# main_module.net
KiCad netlist of a schematic drawn in EAGLE
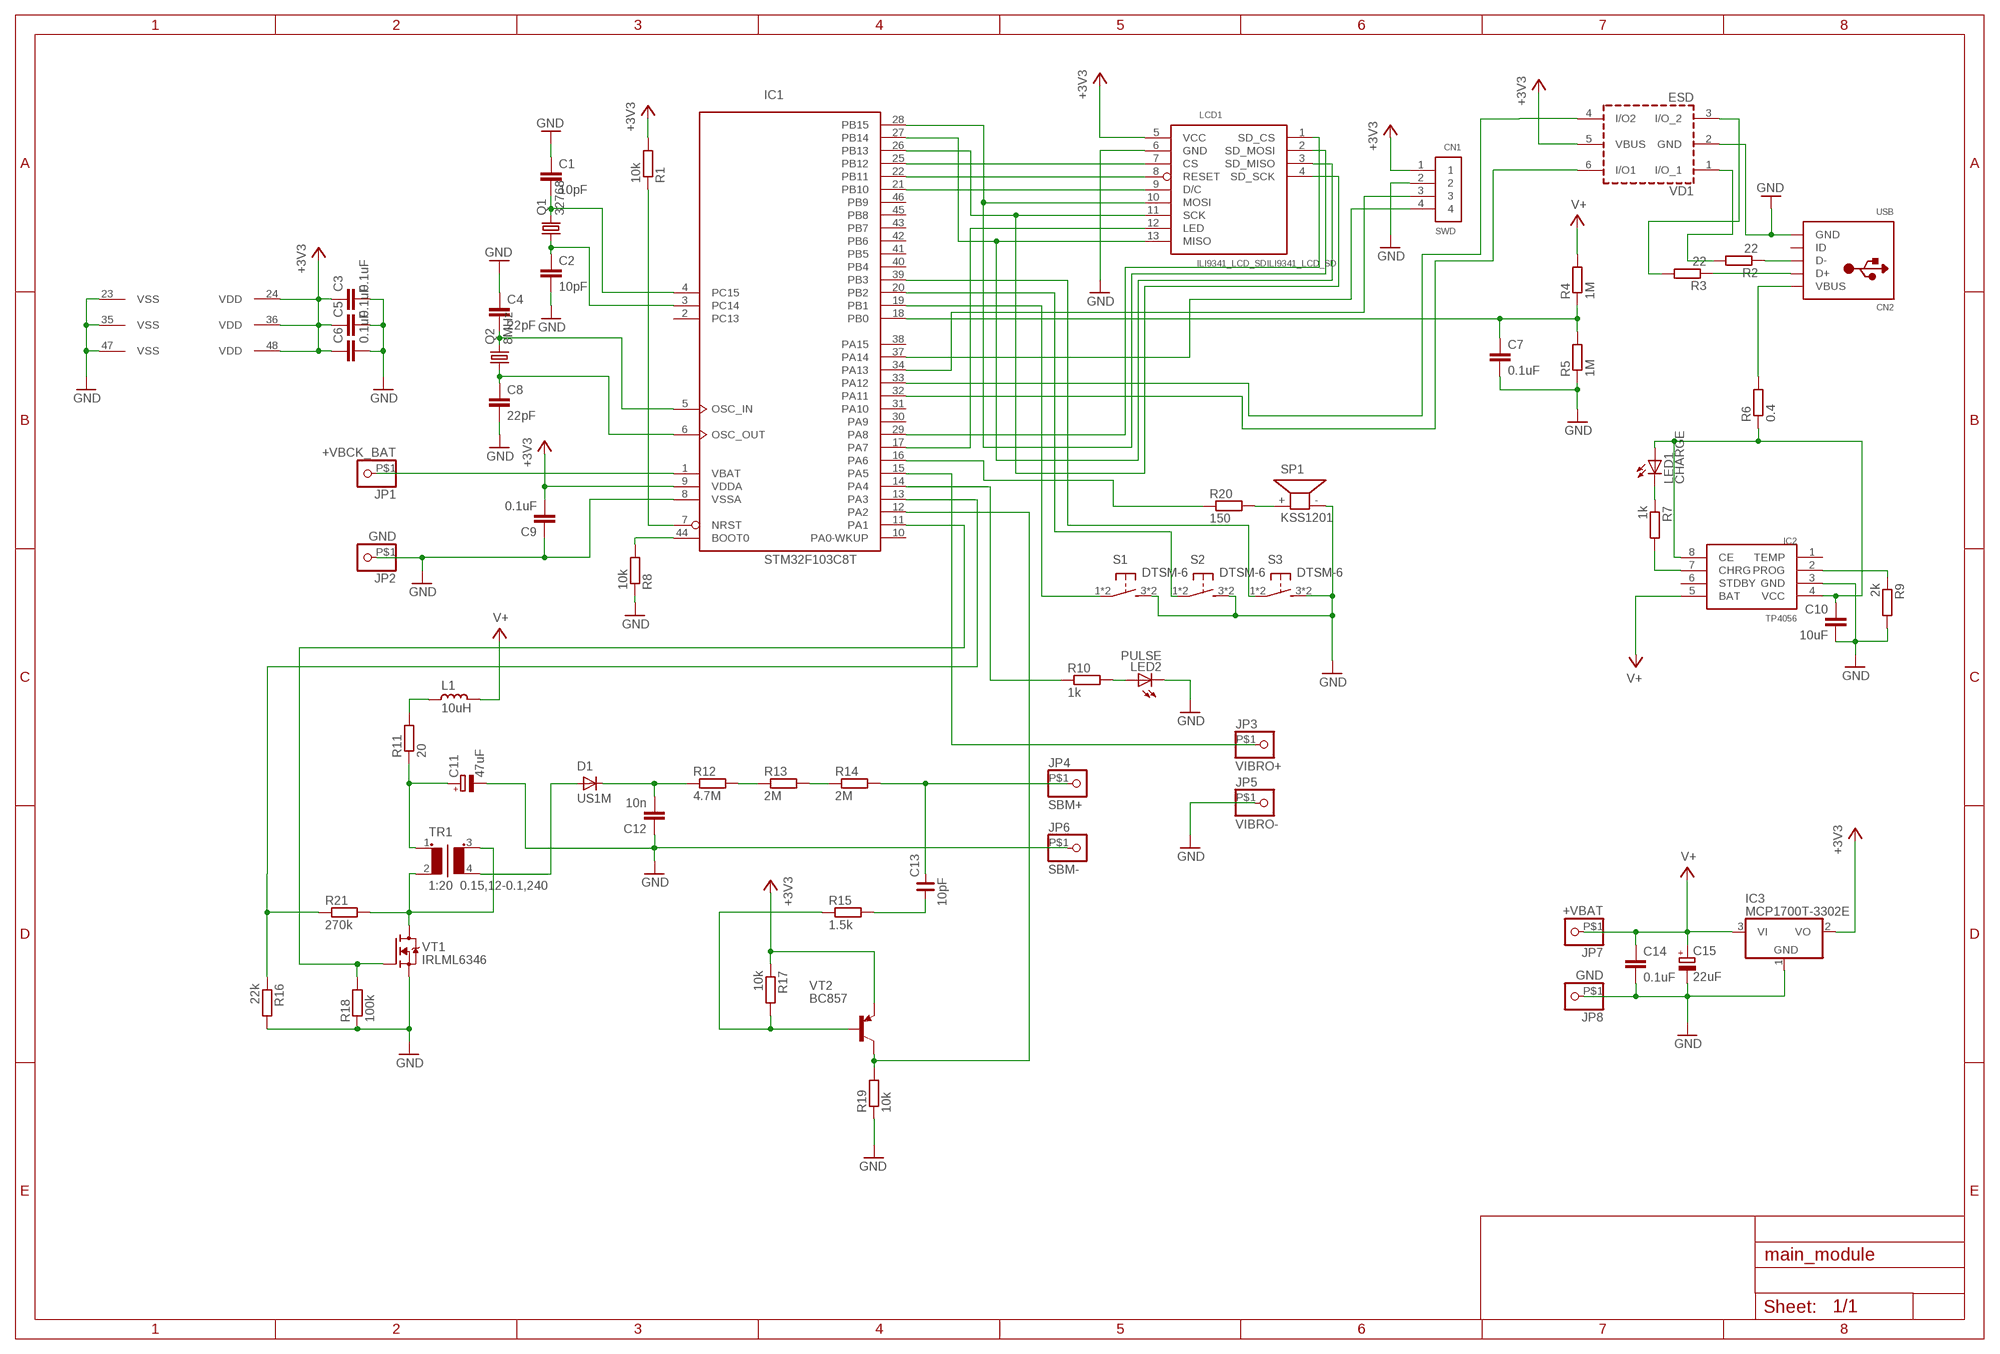
[diagram p0: schematic, sheet 1]

(export (version "E")
  (design (tool "Eeschema 10.0.6"))
  (components
    (comp (ref "C1")
      (value "10pF")
      (footprint "eagle-import:C0805")
      (libsource (lib "eagle-import") (part "C-EUC0805"))
    )
    (comp (ref "C2")
      (value "10pF")
      (footprint "eagle-import:C0805")
      (libsource (lib "eagle-import") (part "C-EUC0805"))
    )
    (comp (ref "C3")
      (value "0.1uF")
      (footprint "eagle-import:C0805")
      (libsource (lib "eagle-import") (part "C-EUC0805"))
    )
    (comp (ref "C4")
      (value "22pF")
      (footprint "eagle-import:C0805")
      (libsource (lib "eagle-import") (part "C-EUC0805"))
    )
    (comp (ref "C5")
      (value "0.1uF")
      (footprint "eagle-import:C0805")
      (libsource (lib "eagle-import") (part "C-EUC0805"))
    )
    (comp (ref "C6")
      (value "0.1uF")
      (footprint "eagle-import:C0805")
      (libsource (lib "eagle-import") (part "C-EUC0805"))
    )
    (comp (ref "C7")
      (value "0.1uF")
      (footprint "eagle-import:C0805")
      (libsource (lib "eagle-import") (part "C-EUC0805"))
    )
    (comp (ref "C8")
      (value "22pF")
      (footprint "eagle-import:C0805")
      (libsource (lib "eagle-import") (part "C-EUC0805"))
    )
    (comp (ref "C9")
      (value "0.1uF")
      (footprint "eagle-import:C0805")
      (libsource (lib "eagle-import") (part "C-EUC0805"))
    )
    (comp (ref "C10")
      (value "10uF")
      (footprint "eagle-import:C0805")
      (libsource (lib "eagle-import") (part "C-EUC0805"))
    )
    (comp (ref "C11")
      (value "47uF")
      (footprint "eagle-import:C_6032-28R")
      (libsource (lib "eagle-import") (part "CPOL-EUC/6032-28R"))
    )
    (comp (ref "C12")
      (value "10n")
      (footprint "eagle-import:C1206")
      (libsource (lib "eagle-import") (part "C-EUC1206"))
    )
    (comp (ref "C13")
      (value "10pF")
      (footprint "eagle-import:C1206")
      (libsource (lib "eagle-import") (part "C_1206"))
    )
    (comp (ref "C14")
      (value "0.1uF")
      (footprint "eagle-import:C0805")
      (libsource (lib "eagle-import") (part "C-EUC0805"))
    )
    (comp (ref "C15")
      (value "22uF")
      (footprint "eagle-import:C_6032-28R")
      (libsource (lib "eagle-import") (part "CPOL-EUC/6032-28R"))
    )
    (comp (ref "CN1")
      (value "SWD")
      (footprint "eagle-import:1X04-BIG")
      (libsource (lib "eagle-import") (part "1X4-BIG"))
    )
    (comp (ref "CN2")
      (value "USB")
      (footprint "eagle-import:USB-MINIB")
      (libsource (lib "eagle-import") (part "USBMINIB"))
    )
    (comp (ref "D1")
      (value "US1M")
      (footprint "eagle-import:SMA-DO214AC")
      (libsource (lib "eagle-import") (part "GF1"))
    )
    (comp (ref "IC1")
      (value "STM32F103C8T")
      (footprint "eagle-import:LQFP48")
      (libsource (lib "eagle-import") (part "STM32F103CT8"))
    )
    (comp (ref "IC2")
      (value "TP4056")
      (footprint "eagle-import:SOP-8")
      (libsource (lib "eagle-import") (part "TP4056"))
    )
    (comp (ref "IC3")
      (value "MCP1700T-3302E")
      (footprint "eagle-import:SOT23")
      (libsource (lib "eagle-import") (part "MCP1703CB"))
    )
    (comp (ref "JP1")
      (value "+VBCK_BAT")
      (footprint "eagle-import:1X1-BIGPOGO")
      (libsource (lib "eagle-import") (part "PINHD-1X1-BIGPOGO"))
    )
    (comp (ref "JP2")
      (value "GND")
      (footprint "eagle-import:1X1-BIGPOGO")
      (libsource (lib "eagle-import") (part "PINHD-1X1-BIGPOGO"))
    )
    (comp (ref "JP3")
      (value "VIBRO+")
      (footprint "eagle-import:1X1-BIGPOGO")
      (libsource (lib "eagle-import") (part "PINHD-1X1-BIGPOGO"))
    )
    (comp (ref "JP4")
      (value "SBM+")
      (footprint "eagle-import:1X1-BIGPOGO")
      (libsource (lib "eagle-import") (part "PINHD-1X1-BIGPOGO"))
    )
    (comp (ref "JP5")
      (value "VIBRO-")
      (footprint "eagle-import:1X1-BIGPOGO")
      (libsource (lib "eagle-import") (part "PINHD-1X1-BIGPOGO"))
    )
    (comp (ref "JP6")
      (value "SBM-")
      (footprint "eagle-import:1X1-BIGPOGO")
      (libsource (lib "eagle-import") (part "PINHD-1X1-BIGPOGO"))
    )
    (comp (ref "JP7")
      (value "+VBAT")
      (footprint "eagle-import:1X1-BIGPOGO")
      (libsource (lib "eagle-import") (part "PINHD-1X1-BIGPOGO"))
    )
    (comp (ref "JP8")
      (value "GND")
      (footprint "eagle-import:1X1-BIGPOGO")
      (libsource (lib "eagle-import") (part "PINHD-1X1-BIGPOGO"))
    )
    (comp (ref "L1")
      (value "10uH")
      (footprint "eagle-import:L0805")
      (libsource (lib "eagle-import") (part "L_0805"))
    )
    (comp (ref "LCD1")
      (value "ILI9341_LCD_SDILI9341_LCD_SD")
      (footprint "eagle-import:ILI9341_LCD_SD")
      (libsource (lib "eagle-import") (part "ILI9341_LCD_SDILI9341_LCD_SD"))
    )
    (comp (ref "LED1")
      (value "CHARGE")
      (footprint "eagle-import:CHIP-LED0805")
      (libsource (lib "eagle-import") (part "led_LEDCHIP-LED0805"))
    )
    (comp (ref "LED2")
      (value "PULSE")
      (footprint "eagle-import:LED3MM")
      (libsource (lib "eagle-import") (part "LED3MM"))
    )
    (comp (ref "Q1")
      (value "32768")
      (footprint "eagle-import:HC49_S")
      (libsource (lib "eagle-import") (part "CRYSTALHC49S"))
    )
    (comp (ref "Q2")
      (value "8MHz")
      (footprint "eagle-import:HC49_S")
      (libsource (lib "eagle-import") (part "CRYSTALHC49S"))
    )
    (comp (ref "R1")
      (value "10k")
      (footprint "eagle-import:M0805")
      (libsource (lib "eagle-import") (part "R-EU_M0805"))
    )
    (comp (ref "R2")
      (value "22")
      (footprint "eagle-import:M0805")
      (libsource (lib "eagle-import") (part "R-EU_M0805"))
    )
    (comp (ref "R3")
      (value "22")
      (footprint "eagle-import:M0805")
      (libsource (lib "eagle-import") (part "R-EU_M0805"))
    )
    (comp (ref "R4")
      (value "1M")
      (footprint "eagle-import:M0805")
      (libsource (lib "eagle-import") (part "R-EU_M0805"))
    )
    (comp (ref "R5")
      (value "1M")
      (footprint "eagle-import:M0805")
      (libsource (lib "eagle-import") (part "R-EU_M0805"))
    )
    (comp (ref "R6")
      (value "0.4")
      (footprint "eagle-import:M1206")
      (libsource (lib "eagle-import") (part "R-EU_M1206"))
    )
    (comp (ref "R7")
      (value "1k")
      (footprint "eagle-import:M0805")
      (libsource (lib "eagle-import") (part "R-EU_M0805"))
    )
    (comp (ref "R8")
      (value "10k")
      (footprint "eagle-import:M0805")
      (libsource (lib "eagle-import") (part "R-EU_M0805"))
    )
    (comp (ref "R9")
      (value "2k")
      (footprint "eagle-import:M0805")
      (libsource (lib "eagle-import") (part "R-EU_M0805"))
    )
    (comp (ref "R10")
      (value "1k")
      (footprint "eagle-import:M0805")
      (libsource (lib "eagle-import") (part "R-EU_M0805"))
    )
    (comp (ref "R11")
      (value "20")
      (footprint "eagle-import:M0805")
      (libsource (lib "eagle-import") (part "R-EU_M0805"))
    )
    (comp (ref "R12")
      (value "4.7M")
      (footprint "eagle-import:M0805")
      (libsource (lib "eagle-import") (part "R-EU_M0805"))
    )
    (comp (ref "R13")
      (value "2M")
      (footprint "eagle-import:M0805")
      (libsource (lib "eagle-import") (part "R-EU_M0805"))
    )
    (comp (ref "R14")
      (value "2M")
      (footprint "eagle-import:M0805")
      (libsource (lib "eagle-import") (part "R-EU_M0805"))
    )
    (comp (ref "R15")
      (value "1.5k")
      (footprint "eagle-import:M0805")
      (libsource (lib "eagle-import") (part "R-EU_M0805"))
    )
    (comp (ref "R16")
      (value "22k")
      (footprint "eagle-import:M0805")
      (libsource (lib "eagle-import") (part "R-EU_M0805"))
    )
    (comp (ref "R17")
      (value "10k")
      (footprint "eagle-import:M0805")
      (libsource (lib "eagle-import") (part "R-EU_M0805"))
    )
    (comp (ref "R18")
      (value "100k")
      (footprint "eagle-import:M0805")
      (libsource (lib "eagle-import") (part "R-EU_M0805"))
    )
    (comp (ref "R19")
      (value "10k")
      (footprint "eagle-import:M0805")
      (libsource (lib "eagle-import") (part "R-EU_M0805"))
    )
    (comp (ref "R20")
      (value "150")
      (footprint "eagle-import:M0805")
      (libsource (lib "eagle-import") (part "R-EU_M0805"))
    )
    (comp (ref "R21")
      (value "270k")
      (footprint "eagle-import:M0805")
      (libsource (lib "eagle-import") (part "R-EU_M0805"))
    )
    (comp (ref "S1")
      (value "DTSM-6")
      (footprint "eagle-import:DTSM-6")
      (libsource (lib "eagle-import") (part "DTSM-6"))
    )
    (comp (ref "S2")
      (value "DTSM-6")
      (footprint "eagle-import:DTSM-6")
      (libsource (lib "eagle-import") (part "DTSM-6"))
    )
    (comp (ref "S3")
      (value "DTSM-6")
      (footprint "eagle-import:DTSM-6")
      (libsource (lib "eagle-import") (part "DTSM-6"))
    )
    (comp (ref "SP1")
      (value "KSS1201")
      (footprint "eagle-import:KSS1201")
      (libsource (lib "eagle-import") (part "KSS1201"))
    )
    (comp (ref "TR1")
      (value "1:20 0.15,12-0.1,240")
      (footprint "eagle-import:RING-TRANS")
      (libsource (lib "eagle-import") (part "RING-TRANS"))
    )
    (comp (ref "VD1")
      (value "ESD")
      (footprint "eagle-import:SOT-23-6L")
      (libsource (lib "eagle-import") (part "USBLC6-2SC6"))
    )
    (comp (ref "VT1")
      (value "IRLML6346")
      (footprint "eagle-import:SOT23")
      (libsource (lib "eagle-import") (part "MOSFET-N-SOT23"))
    )
    (comp (ref "VT2")
      (value "BC857")
      (footprint "eagle-import:SOT23-BCE")
      (libsource (lib "eagle-import") (part "-PNP-SOT23-BCE"))
    )
  )
  (nets
    (net (code "1") (name "+3V3") (class "Default")
      (node (ref "C3") (pin "1") (pinfunction "1_1") (pintype "passive"))
      (node (ref "C5") (pin "1") (pinfunction "1_1") (pintype "passive"))
      (node (ref "C6") (pin "1") (pinfunction "1_1") (pintype "passive"))
      (node (ref "C9") (pin "2") (pinfunction "2_2") (pintype "passive"))
      (node (ref "CN1") (pin "1") (pinfunction "1_1") (pintype "bidirectional"))
      (node (ref "IC1") (pin "24") (pinfunction "VDD_24") (pintype "power_in"))
      (node (ref "IC1") (pin "36") (pinfunction "VDD_36") (pintype "power_in"))
      (node (ref "IC1") (pin "48") (pinfunction "VDD_48") (pintype "power_in"))
      (node (ref "IC1") (pin "9") (pinfunction "VDDA_9") (pintype "power_in"))
      (node (ref "IC3") (pin "2") (pinfunction "VO_2") (pintype "passive"))
      (node (ref "LCD1") (pin "5") (pinfunction "VCC_5") (pintype "power_in"))
      (node (ref "R1") (pin "2") (pinfunction "2_2") (pintype "passive"))
      (node (ref "R17") (pin "1") (pinfunction "1_1") (pintype "passive"))
      (node (ref "VD1") (pin "5") (pinfunction "VBUS_5") (pintype "bidirectional"))
      (node (ref "VT2") (pin "E") (pinfunction "E_E") (pintype "passive"))
    )
    (net (code "2") (name "GND") (class "Default")
      (node (ref "C1") (pin "1") (pinfunction "1_1") (pintype "passive"))
      (node (ref "C10") (pin "2") (pinfunction "2_2") (pintype "passive"))
      (node (ref "C11") (pin "-") (pinfunction "-_-") (pintype "passive"))
      (node (ref "C12") (pin "1") (pinfunction "1_1") (pintype "passive"))
      (node (ref "C14") (pin "2") (pinfunction "2_2") (pintype "passive"))
      (node (ref "C15") (pin "-") (pinfunction "-_-") (pintype "passive"))
      (node (ref "C2") (pin "2") (pinfunction "2_2") (pintype "passive"))
      (node (ref "C3") (pin "2") (pinfunction "2_2") (pintype "passive"))
      (node (ref "C4") (pin "1") (pinfunction "1_1") (pintype "passive"))
      (node (ref "C5") (pin "2") (pinfunction "2_2") (pintype "passive"))
      (node (ref "C6") (pin "2") (pinfunction "2_2") (pintype "passive"))
      (node (ref "C7") (pin "2") (pinfunction "2_2") (pintype "passive"))
      (node (ref "C8") (pin "2") (pinfunction "2_2") (pintype "passive"))
      (node (ref "C9") (pin "1") (pinfunction "1_1") (pintype "passive"))
      (node (ref "CN1") (pin "2") (pinfunction "2_2") (pintype "bidirectional"))
      (node (ref "CN2") (pin "GND") (pinfunction "GND_GND") (pintype "power_in"))
      (node (ref "IC1") (pin "23") (pinfunction "VSS_23") (pintype "power_in"))
      (node (ref "IC1") (pin "35") (pinfunction "VSS_35") (pintype "power_in"))
      (node (ref "IC1") (pin "47") (pinfunction "VSS_47") (pintype "power_in"))
      (node (ref "IC1") (pin "8") (pinfunction "VSSA_8") (pintype "power_in"))
      (node (ref "IC2") (pin "3") (pinfunction "GND_3") (pintype "bidirectional"))
      (node (ref "IC3") (pin "1") (pinfunction "GND_1") (pintype "passive"))
      (node (ref "JP2") (pin "P$1") (pinfunction "1_P$1") (pintype "passive"))
      (node (ref "JP5") (pin "P$1") (pinfunction "1_P$1") (pintype "passive"))
      (node (ref "JP6") (pin "P$1") (pinfunction "1_P$1") (pintype "passive"))
      (node (ref "JP8") (pin "P$1") (pinfunction "1_P$1") (pintype "passive"))
      (node (ref "LCD1") (pin "6") (pinfunction "GND_6") (pintype "power_in"))
      (node (ref "LED2") (pin "K") (pinfunction "C_K") (pintype "passive"))
      (node (ref "R16") (pin "2") (pinfunction "2_2") (pintype "passive"))
      (node (ref "R18") (pin "1") (pinfunction "1_1") (pintype "passive"))
      (node (ref "R19") (pin "1") (pinfunction "1_1") (pintype "passive"))
      (node (ref "R5") (pin "1") (pinfunction "1_1") (pintype "passive"))
      (node (ref "R8") (pin "1") (pinfunction "1_1") (pintype "passive"))
      (node (ref "R9") (pin "2") (pinfunction "2_2") (pintype "passive"))
      (node (ref "S1") (pin "3") (pinfunction "3_3") (pintype "passive"))
      (node (ref "S1") (pin "4") (pinfunction "3_4") (pintype "passive"))
      (node (ref "S2") (pin "3") (pinfunction "3_3") (pintype "passive"))
      (node (ref "S2") (pin "4") (pinfunction "3_4") (pintype "passive"))
      (node (ref "S3") (pin "3") (pinfunction "3_3") (pintype "passive"))
      (node (ref "S3") (pin "4") (pinfunction "3_4") (pintype "passive"))
      (node (ref "SP1") (pin "-") (pinfunction "2_-") (pintype "passive"))
      (node (ref "VD1") (pin "2") (pinfunction "GND_2") (pintype "bidirectional"))
      (node (ref "VT1") (pin "2") (pinfunction "S_2") (pintype "passive"))
    )
    (net (code "3") (name "Net-(C13-Pad1)") (class "Default")
      (node (ref "C13") (pin "1") (pinfunction "1_1") (pintype "passive"))
      (node (ref "R15") (pin "2") (pinfunction "2_2") (pintype "passive"))
    )
    (net (code "4") (name "Net-(CN2-PadD+)") (class "Default")
      (node (ref "CN2") (pin "D+") (pinfunction "D+_D+") (pintype "bidirectional"))
      (node (ref "R3") (pin "1") (pinfunction "1_1") (pintype "passive"))
    )
    (net (code "5") (name "Net-(CN2-PadD-)") (class "Default")
      (node (ref "CN2") (pin "D-") (pinfunction "D-_D-") (pintype "bidirectional"))
      (node (ref "R2") (pin "1") (pinfunction "1_1") (pintype "passive"))
    )
    (net (code "6") (name "Net-(CN2-PadVBUS)") (class "Default")
      (node (ref "CN2") (pin "VBUS") (pinfunction "VBUS_VBUS") (pintype "power_in"))
      (node (ref "R6") (pin "2") (pinfunction "2_2") (pintype "passive"))
    )
    (net (code "7") (name "Net-(D1-C)") (class "Default")
      (node (ref "C12") (pin "2") (pinfunction "2_2") (pintype "passive"))
      (node (ref "D1") (pin "K") (pinfunction "C_K") (pintype "passive"))
      (node (ref "R12") (pin "1") (pinfunction "1_1") (pintype "passive"))
    )
    (net (code "8") (name "Net-(IC1A-BOOT0)") (class "Default")
      (node (ref "IC1") (pin "44") (pinfunction "BOOT0_44") (pintype "input"))
      (node (ref "R8") (pin "2") (pinfunction "2_2") (pintype "passive"))
    )
    (net (code "9") (name "Net-(IC1A-NRST)") (class "Default")
      (node (ref "IC1") (pin "7") (pinfunction "NRST_7") (pintype "bidirectional"))
      (node (ref "R1") (pin "1") (pinfunction "1_1") (pintype "passive"))
    )
    (net (code "10") (name "Net-(IC1A-OSC_IN)") (class "Default")
      (node (ref "C4") (pin "2") (pinfunction "2_2") (pintype "passive"))
      (node (ref "IC1") (pin "5") (pinfunction "OSC_IN_5") (pintype "bidirectional"))
      (node (ref "Q2") (pin "2") (pinfunction "2_2") (pintype "passive"))
    )
    (net (code "11") (name "Net-(IC1A-OSC_OUT)") (class "Default")
      (node (ref "C8") (pin "1") (pinfunction "1_1") (pintype "passive"))
      (node (ref "IC1") (pin "6") (pinfunction "OSC_OUT_6") (pintype "bidirectional"))
      (node (ref "Q2") (pin "1") (pinfunction "1_1") (pintype "passive"))
    )
    (net (code "12") (name "Net-(IC1A-PA1)") (class "Default")
      (node (ref "IC1") (pin "11") (pinfunction "PA1_11") (pintype "bidirectional"))
      (node (ref "R18") (pin "2") (pinfunction "2_2") (pintype "passive"))
      (node (ref "VT1") (pin "1") (pinfunction "G_1") (pintype "passive"))
    )
    (net (code "13") (name "Net-(IC1A-PA2)") (class "Default")
      (node (ref "IC1") (pin "12") (pinfunction "PA2_12") (pintype "bidirectional"))
      (node (ref "R19") (pin "2") (pinfunction "2_2") (pintype "passive"))
      (node (ref "VT2") (pin "C") (pinfunction "C_C") (pintype "passive"))
    )
    (net (code "14") (name "Net-(IC1A-PA3)") (class "Default")
      (node (ref "IC1") (pin "13") (pinfunction "PA3_13") (pintype "bidirectional"))
      (node (ref "R16") (pin "1") (pinfunction "1_1") (pintype "passive"))
      (node (ref "R21") (pin "1") (pinfunction "1_1") (pintype "passive"))
    )
    (net (code "15") (name "Net-(IC1A-PA4)") (class "Default")
      (node (ref "IC1") (pin "14") (pinfunction "PA4_14") (pintype "bidirectional"))
      (node (ref "R10") (pin "1") (pinfunction "1_1") (pintype "passive"))
    )
    (net (code "16") (name "Net-(IC1A-PA5)") (class "Default")
      (node (ref "IC1") (pin "15") (pinfunction "PA5_15") (pintype "bidirectional"))
      (node (ref "JP3") (pin "P$1") (pinfunction "1_P$1") (pintype "passive"))
    )
    (net (code "17") (name "Net-(IC1A-PA6)") (class "Default")
      (node (ref "IC1") (pin "16") (pinfunction "PA6_16") (pintype "bidirectional"))
      (node (ref "R20") (pin "1") (pinfunction "1_1") (pintype "passive"))
    )
    (net (code "18") (name "Net-(IC1A-PA7)") (class "Default")
      (node (ref "IC1") (pin "17") (pinfunction "PA7_17") (pintype "bidirectional"))
      (node (ref "LCD1") (pin "12") (pinfunction "LED_12") (pintype "input"))
    )
    (net (code "19") (name "Net-(IC1A-PA8)") (class "Default")
      (node (ref "IC1") (pin "29") (pinfunction "PA8_29") (pintype "bidirectional"))
      (node (ref "LCD1") (pin "1") (pinfunction "SD_CS_1") (pintype "input"))
    )
    (net (code "20") (name "Net-(IC1A-PA11)") (class "Default")
      (node (ref "IC1") (pin "32") (pinfunction "PA11_32") (pintype "bidirectional"))
      (node (ref "VD1") (pin "6") (pinfunction "I/O1_6") (pintype "bidirectional"))
    )
    (net (code "21") (name "Net-(IC1A-PA12)") (class "Default")
      (node (ref "IC1") (pin "33") (pinfunction "PA12_33") (pintype "bidirectional"))
      (node (ref "VD1") (pin "4") (pinfunction "I/O2_4") (pintype "bidirectional"))
    )
    (net (code "22") (name "Net-(IC1A-PA13)") (class "Default")
      (node (ref "CN1") (pin "3") (pinfunction "3_3") (pintype "bidirectional"))
      (node (ref "IC1") (pin "34") (pinfunction "PA13_34") (pintype "bidirectional"))
    )
    (net (code "23") (name "Net-(IC1A-PA14)") (class "Default")
      (node (ref "CN1") (pin "4") (pinfunction "4_4") (pintype "bidirectional"))
      (node (ref "IC1") (pin "37") (pinfunction "PA14_37") (pintype "bidirectional"))
    )
    (net (code "24") (name "Net-(IC1A-PB0)") (class "Default")
      (node (ref "C7") (pin "1") (pinfunction "1_1") (pintype "passive"))
      (node (ref "IC1") (pin "18") (pinfunction "PB0_18") (pintype "bidirectional"))
      (node (ref "R4") (pin "1") (pinfunction "1_1") (pintype "passive"))
      (node (ref "R5") (pin "2") (pinfunction "2_2") (pintype "passive"))
    )
    (net (code "25") (name "Net-(IC1A-PB1)") (class "Default")
      (node (ref "IC1") (pin "19") (pinfunction "PB1_19") (pintype "bidirectional"))
      (node (ref "S1") (pin "1") (pinfunction "1_1") (pintype "passive"))
      (node (ref "S1") (pin "2") (pinfunction "1_2") (pintype "passive"))
    )
    (net (code "26") (name "Net-(IC1A-PB2)") (class "Default")
      (node (ref "IC1") (pin "20") (pinfunction "PB2_20") (pintype "bidirectional"))
      (node (ref "S2") (pin "1") (pinfunction "1_1") (pintype "passive"))
      (node (ref "S2") (pin "2") (pinfunction "1_2") (pintype "passive"))
    )
    (net (code "27") (name "Net-(IC1A-PB3)") (class "Default")
      (node (ref "IC1") (pin "39") (pinfunction "PB3_39") (pintype "bidirectional"))
      (node (ref "S3") (pin "1") (pinfunction "1_1") (pintype "passive"))
      (node (ref "S3") (pin "2") (pinfunction "1_2") (pintype "passive"))
    )
    (net (code "28") (name "Net-(IC1A-PB10)") (class "Default")
      (node (ref "IC1") (pin "21") (pinfunction "PB10_21") (pintype "bidirectional"))
      (node (ref "LCD1") (pin "9") (pinfunction "D/C_9") (pintype "input"))
    )
    (net (code "29") (name "Net-(IC1A-PB11)") (class "Default")
      (node (ref "IC1") (pin "22") (pinfunction "PB11_22") (pintype "bidirectional"))
      (node (ref "LCD1") (pin "8") (pinfunction "RESET_8") (pintype "input"))
    )
    (net (code "30") (name "Net-(IC1A-PB12)") (class "Default")
      (node (ref "IC1") (pin "25") (pinfunction "PB12_25") (pintype "bidirectional"))
      (node (ref "LCD1") (pin "7") (pinfunction "CS_7") (pintype "input"))
    )
    (net (code "31") (name "Net-(IC1A-PB13)") (class "Default")
      (node (ref "IC1") (pin "26") (pinfunction "PB13_26") (pintype "bidirectional"))
      (node (ref "LCD1") (pin "11") (pinfunction "SCK_11") (pintype "input"))
      (node (ref "LCD1") (pin "4") (pinfunction "SD_SCK_4") (pintype "input"))
    )
    (net (code "32") (name "Net-(IC1A-PB14)") (class "Default")
      (node (ref "IC1") (pin "27") (pinfunction "PB14_27") (pintype "bidirectional"))
      (node (ref "LCD1") (pin "13") (pinfunction "MISO_13") (pintype "bidirectional"))
      (node (ref "LCD1") (pin "3") (pinfunction "SD_MISO_3") (pintype "bidirectional"))
    )
    (net (code "33") (name "Net-(IC1A-PB15)") (class "Default")
      (node (ref "IC1") (pin "28") (pinfunction "PB15_28") (pintype "bidirectional"))
      (node (ref "LCD1") (pin "10") (pinfunction "MOSI_10") (pintype "bidirectional"))
      (node (ref "LCD1") (pin "2") (pinfunction "SD_MOSI_2") (pintype "bidirectional"))
    )
    (net (code "34") (name "Net-(IC1A-PC14)") (class "Default")
      (node (ref "C2") (pin "1") (pinfunction "1_1") (pintype "passive"))
      (node (ref "IC1") (pin "3") (pinfunction "PC14_3") (pintype "bidirectional"))
      (node (ref "Q1") (pin "1") (pinfunction "1_1") (pintype "passive"))
    )
    (net (code "35") (name "Net-(IC1A-PC15)") (class "Default")
      (node (ref "C1") (pin "2") (pinfunction "2_2") (pintype "passive"))
      (node (ref "IC1") (pin "4") (pinfunction "PC15_4") (pintype "bidirectional"))
      (node (ref "Q1") (pin "2") (pinfunction "2_2") (pintype "passive"))
    )
    (net (code "36") (name "Net-(IC1A-VBAT)") (class "Default")
      (node (ref "IC1") (pin "1") (pinfunction "VBAT_1") (pintype "power_in"))
      (node (ref "JP1") (pin "P$1") (pinfunction "1_P$1") (pintype "passive"))
    )
    (net (code "37") (name "Net-(IC2-CE)") (class "Default")
      (node (ref "C10") (pin "1") (pinfunction "1_1") (pintype "passive"))
      (node (ref "IC2") (pin "4") (pinfunction "VCC_4") (pintype "bidirectional"))
      (node (ref "IC2") (pin "8") (pinfunction "CE_8") (pintype "bidirectional"))
      (node (ref "LED1") (pin "A") (pinfunction "A_A") (pintype "passive"))
      (node (ref "R6") (pin "1") (pinfunction "1_1") (pintype "passive"))
    )
    (net (code "38") (name "Net-(IC2-CHRG)") (class "Default")
      (node (ref "IC2") (pin "7") (pinfunction "CHRG_7") (pintype "bidirectional"))
      (node (ref "R7") (pin "2") (pinfunction "2_2") (pintype "passive"))
    )
    (net (code "39") (name "Net-(IC2-PROG)") (class "Default")
      (node (ref "IC2") (pin "2") (pinfunction "PROG_2") (pintype "bidirectional"))
      (node (ref "R9") (pin "1") (pinfunction "1_1") (pintype "passive"))
    )
    (net (code "40") (name "Net-(JP4-1)") (class "Default")
      (node (ref "C13") (pin "2") (pinfunction "2_2") (pintype "passive"))
      (node (ref "JP4") (pin "P$1") (pinfunction "1_P$1") (pintype "passive"))
      (node (ref "R14") (pin "2") (pinfunction "2_2") (pintype "passive"))
    )
    (net (code "41") (name "Net-(L1-Pad2)") (class "Default")
      (node (ref "L1") (pin "2") (pinfunction "2_2") (pintype "passive"))
      (node (ref "R11") (pin "2") (pinfunction "2_2") (pintype "passive"))
    )
    (net (code "42") (name "Net-(LED1-PadC)") (class "Default")
      (node (ref "LED1") (pin "C") (pinfunction "C_C") (pintype "passive"))
      (node (ref "R7") (pin "1") (pinfunction "1_1") (pintype "passive"))
    )
    (net (code "43") (name "Net-(LED2-PadA)") (class "Default")
      (node (ref "LED2") (pin "A") (pinfunction "A_A") (pintype "passive"))
      (node (ref "R10") (pin "2") (pinfunction "2_2") (pintype "passive"))
    )
    (net (code "44") (name "Net-(R12-Pad2)") (class "Default")
      (node (ref "R12") (pin "2") (pinfunction "2_2") (pintype "passive"))
      (node (ref "R13") (pin "1") (pinfunction "1_1") (pintype "passive"))
    )
    (net (code "45") (name "Net-(R13-Pad2)") (class "Default")
      (node (ref "R13") (pin "2") (pinfunction "2_2") (pintype "passive"))
      (node (ref "R14") (pin "1") (pinfunction "1_1") (pintype "passive"))
    )
    (net (code "46") (name "Net-(R15-Pad1)") (class "Default")
      (node (ref "R15") (pin "1") (pinfunction "1_1") (pintype "passive"))
      (node (ref "R17") (pin "2") (pinfunction "2_2") (pintype "passive"))
      (node (ref "VT2") (pin "B") (pinfunction "B_B") (pintype "passive"))
    )
    (net (code "47") (name "Net-(SP1-1)") (class "Default")
      (node (ref "R20") (pin "2") (pinfunction "2_2") (pintype "passive"))
      (node (ref "SP1") (pin "+") (pinfunction "1_+") (pintype "passive"))
    )
    (net (code "48") (name "Net-(TR1-P1)") (class "Default")
      (node (ref "C11") (pin "+") (pinfunction "+_+") (pintype "passive"))
      (node (ref "R11") (pin "1") (pinfunction "1_1") (pintype "passive"))
      (node (ref "TR1") (pin "1") (pinfunction "P1_1") (pintype "passive"))
    )
    (net (code "49") (name "Net-(TR1-P2)") (class "Default")
      (node (ref "R21") (pin "2") (pinfunction "2_2") (pintype "passive"))
      (node (ref "TR1") (pin "2") (pinfunction "P2_2") (pintype "passive"))
      (node (ref "TR1") (pin "3") (pinfunction "S1_3") (pintype "passive"))
      (node (ref "VT1") (pin "3") (pinfunction "D_3") (pintype "passive"))
    )
    (net (code "50") (name "Net-(TR1-S2)") (class "Default")
      (node (ref "D1") (pin "A") (pinfunction "A_A") (pintype "passive"))
      (node (ref "TR1") (pin "4") (pinfunction "S2_4") (pintype "passive"))
    )
    (net (code "51") (name "Net-(VD1-I{slash}O_1)") (class "Default")
      (node (ref "R2") (pin "2") (pinfunction "2_2") (pintype "passive"))
      (node (ref "VD1") (pin "1") (pinfunction "I/O_1_1") (pintype "bidirectional"))
    )
    (net (code "52") (name "Net-(VD1-I{slash}O_2)") (class "Default")
      (node (ref "R3") (pin "2") (pinfunction "2_2") (pintype "passive"))
      (node (ref "VD1") (pin "3") (pinfunction "I/O_2_3") (pintype "bidirectional"))
    )
    (net (code "53") (name "V+") (class "Default")
      (node (ref "C14") (pin "1") (pinfunction "1_1") (pintype "passive"))
      (node (ref "C15") (pin "+") (pinfunction "+_+") (pintype "passive"))
      (node (ref "IC2") (pin "5") (pinfunction "BAT_5") (pintype "bidirectional"))
      (node (ref "IC3") (pin "3") (pinfunction "VI_3") (pintype "input"))
      (node (ref "JP7") (pin "P$1") (pinfunction "1_P$1") (pintype "passive"))
      (node (ref "L1") (pin "1") (pinfunction "1_1") (pintype "passive"))
      (node (ref "R4") (pin "2") (pinfunction "2_2") (pintype "passive"))
    )
    (net (code "54") (name "unconnected-(CN2-PadID)") (class "Default")
      (node (ref "CN2") (pin "ID") (pinfunction "ID_ID") (pintype "bidirectional"))
    )
    (net (code "55") (name "unconnected-(IC1A-PA0-WKUP-Pad10)") (class "Default")
      (node (ref "IC1") (pin "10") (pinfunction "PA0-WKUP_10") (pintype "bidirectional"))
    )
    (net (code "56") (name "unconnected-(IC1A-PA9-Pad30)") (class "Default")
      (node (ref "IC1") (pin "30") (pinfunction "PA9_30") (pintype "bidirectional"))
    )
    (net (code "57") (name "unconnected-(IC1A-PA10-Pad31)") (class "Default")
      (node (ref "IC1") (pin "31") (pinfunction "PA10_31") (pintype "bidirectional"))
    )
    (net (code "58") (name "unconnected-(IC1A-PA15-Pad38)") (class "Default")
      (node (ref "IC1") (pin "38") (pinfunction "PA15_38") (pintype "bidirectional"))
    )
    (net (code "59") (name "unconnected-(IC1A-PB4-Pad40)") (class "Default")
      (node (ref "IC1") (pin "40") (pinfunction "PB4_40") (pintype "bidirectional"))
    )
    (net (code "60") (name "unconnected-(IC1A-PB5-Pad41)") (class "Default")
      (node (ref "IC1") (pin "41") (pinfunction "PB5_41") (pintype "bidirectional"))
    )
    (net (code "61") (name "unconnected-(IC1A-PB6-Pad42)") (class "Default")
      (node (ref "IC1") (pin "42") (pinfunction "PB6_42") (pintype "bidirectional"))
    )
    (net (code "62") (name "unconnected-(IC1A-PB7-Pad43)") (class "Default")
      (node (ref "IC1") (pin "43") (pinfunction "PB7_43") (pintype "bidirectional"))
    )
    (net (code "63") (name "unconnected-(IC1A-PB8-Pad45)") (class "Default")
      (node (ref "IC1") (pin "45") (pinfunction "PB8_45") (pintype "bidirectional"))
    )
    (net (code "64") (name "unconnected-(IC1A-PB9-Pad46)") (class "Default")
      (node (ref "IC1") (pin "46") (pinfunction "PB9_46") (pintype "bidirectional"))
    )
    (net (code "65") (name "unconnected-(IC1A-PC13-Pad2)") (class "Default")
      (node (ref "IC1") (pin "2") (pinfunction "PC13_2") (pintype "bidirectional"))
    )
    (net (code "66") (name "unconnected-(IC2-STDBY-Pad6)") (class "Default")
      (node (ref "IC2") (pin "6") (pinfunction "STDBY_6") (pintype "bidirectional"))
    )
    (net (code "67") (name "unconnected-(IC2-TEMP-Pad1)") (class "Default")
      (node (ref "IC2") (pin "1") (pinfunction "TEMP_1") (pintype "bidirectional"))
    )
  )
)
